# CLOCKANDSWITCH.net
KiCad netlist of a schematic drawn in Altium Designer
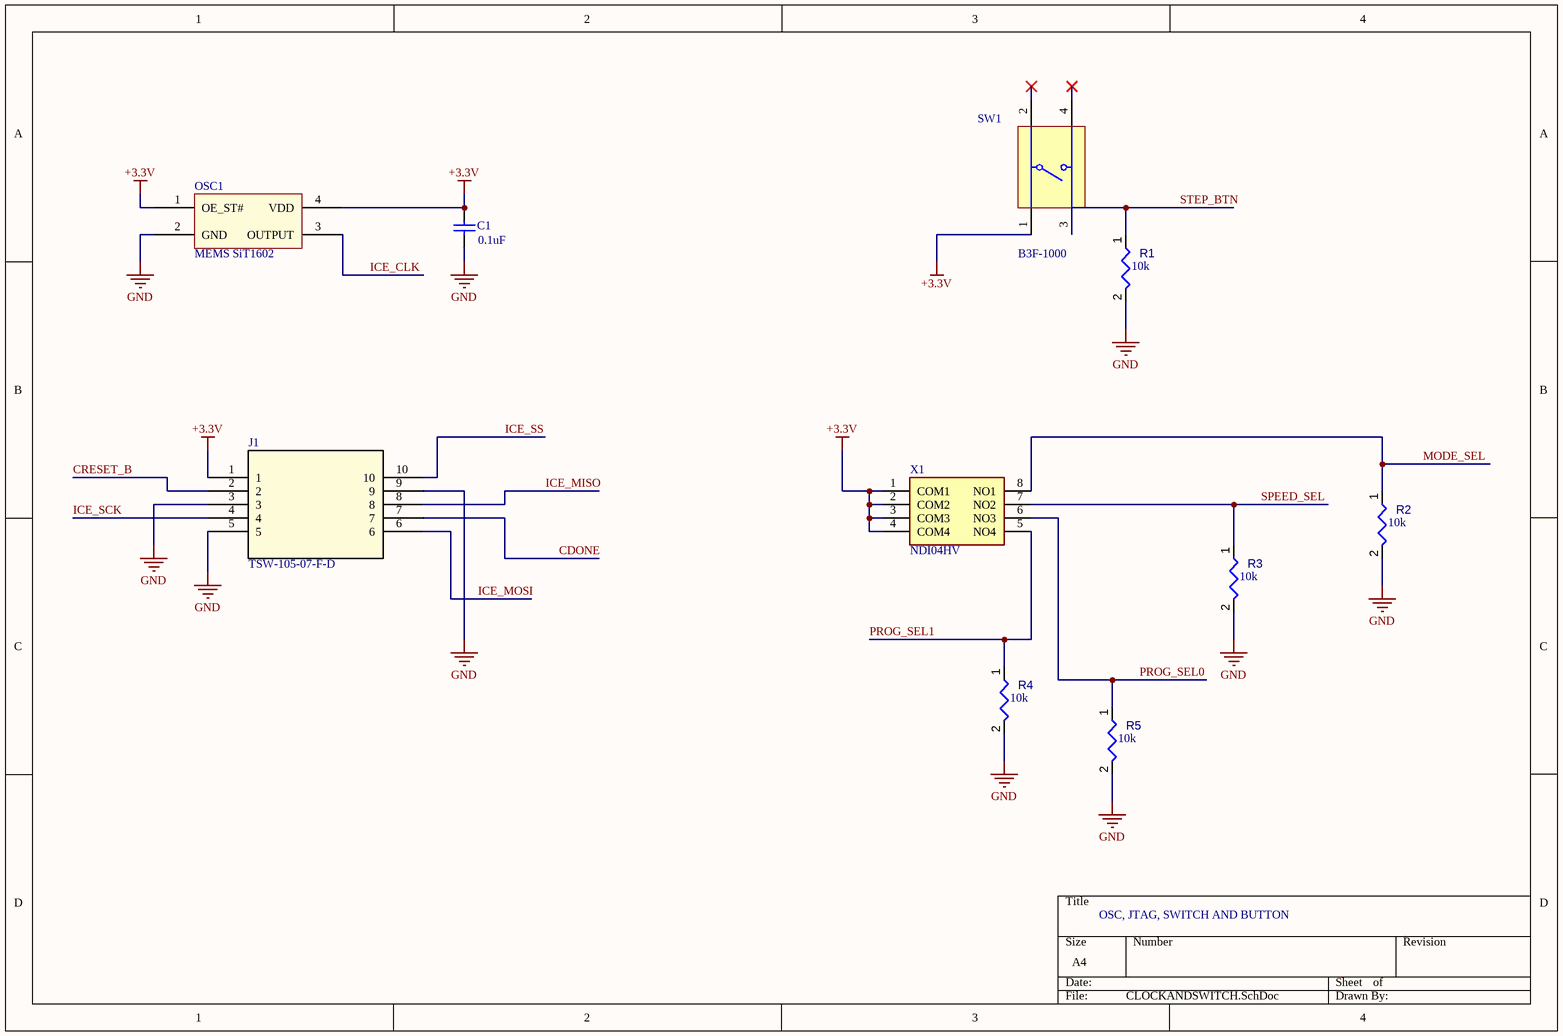
[diagram p0: CLOCKANDSWITCH.SchDoc]

(export (version "E")
  (design (tool "Eeschema 10.0.6"))
  (components
    (comp (ref "C1")
      (value "0.1uF")
      (footprint "C0402")
      (description "Capacitor (Semiconductor SIM Model)")
      (fields
        (field (name "MANUFACTURER") "Samsung Electro-Mechanics")
        (field (name "MANUFACTURER PART NUMBER") "CL05B104KA5NNNC")
        (field (name "PUBLISHER") "Altium Limited")
      )
      (libsource (lib "Miscellaneous Devices") (part "Cap Semi"))
    )
    (comp (ref "J1")
      (value "TSW-105-07-F-D")
      (footprint "TSW-105-07-G-D_SAI")
      (description "Description")
      (fields (field (name "COPYRIGHT") "Copyright (C) 2025 Ultra Librarian. All rights reserved."))
      (libsource (lib "Talha Khan") (part "TSW-105-07-F-D"))
    )
    (comp (ref "OSC1")
      (value "MEMS SiT1602")
      (footprint "oscMEMS1602")
      (description "MEMS OSC XO 12.0000MHZ LVCMOS")
      (fields
        (field (name "MANUFACTURER") "SiTIME")
        (field (name "MANUFACTURER PART NUMBER") "SIT1602AC-13-33E-12.000000G")
      )
      (libsource (lib "FPGAlib") (part "SIT1602AC-13-33E-12.000000G"))
    )
    (comp (ref "R1")
      (value "10k")
      (footprint "RESC2013X50X35ML15T15")
      (description "Chip Resistor, 10 KOhm, +/- 1%, 125 mW, -55 to 155 degC, 0805 (2012 Metric)")
      (fields (field (name "TOLERANCE") "1%") (field (name "POWER") "125mW"))
      (libsource (lib "Talha Khan") (part "RES-2"))
    )
    (comp (ref "R2")
      (value "10k")
      (footprint "RESC2013X50X35ML15T15")
      (description "Chip Resistor, 10 KOhm, +/- 1%, 125 mW, -55 to 155 degC, 0805 (2012 Metric)")
      (fields (field (name "TOLERANCE") "1%") (field (name "POWER") "125mW"))
      (libsource (lib "Talha Khan") (part "RES-2"))
    )
    (comp (ref "R3")
      (value "10k")
      (footprint "RESC2013X50X35ML15T15")
      (description "Chip Resistor, 10 KOhm, +/- 1%, 125 mW, -55 to 155 degC, 0805 (2012 Metric)")
      (fields (field (name "TOLERANCE") "1%") (field (name "POWER") "125mW"))
      (libsource (lib "Talha Khan") (part "RES-2"))
    )
    (comp (ref "R4")
      (value "10k")
      (footprint "RESC2013X50X35ML15T15")
      (description "Chip Resistor, 10 KOhm, +/- 1%, 125 mW, -55 to 155 degC, 0805 (2012 Metric)")
      (fields (field (name "TOLERANCE") "1%") (field (name "POWER") "125mW"))
      (libsource (lib "Talha Khan") (part "RES-2"))
    )
    (comp (ref "R5")
      (value "10k")
      (footprint "RESC2013X50X35ML15T15")
      (description "Chip Resistor, 10 KOhm, +/- 1%, 125 mW, -55 to 155 degC, 0805 (2012 Metric)")
      (fields (field (name "TOLERANCE") "1%") (field (name "POWER") "125mW"))
      (libsource (lib "Talha Khan") (part "RES-2"))
    )
    (comp (ref "SW1")
      (value "B3F-1000")
      (footprint "OMRON-B3F-1000-4_V")
      (description "Tactile Switch, SPST-NO, 0.05 A, 24 V, -25 to 70 degC, 4-Pin THD, RoHS, Bulk")
      (fields (field (name "MANUFACTURER") "Omron Electronic Components"))
      (libsource (lib "Talha Khan") (part "SW-SPST-4_A"))
    )
    (comp (ref "X1")
      (value "NDI04HV")
      (footprint "NDI04HV")
      (description "Dip Switch SPST 4 Position Through Hole Slide (Standard) Actuator 25mA 24VDC")
      (fields (field (name "MOUSER PART NUMBER") "642-NDI04HV"))
      (libsource (lib "Talha Khan") (part "NDI04HV"))
    )
  )
  (nets
    (net (code "1") (name "+3.3V") (class "Default")
      (node (ref "C1") (pin "2") (pinfunction "2_2") (pintype "passive"))
      (node (ref "J1") (pin "1") (pinfunction "1_1") (pintype "passive"))
      (node (ref "OSC1") (pin "1") (pinfunction "OE_ST#_1") (pintype "passive"))
      (node (ref "OSC1") (pin "4") (pinfunction "VDD_4") (pintype "passive"))
      (node (ref "SW1") (pin "1") (pinfunction "1_1") (pintype "passive"))
      (node (ref "X1") (pin "1") (pinfunction "COM1_1") (pintype "passive"))
      (node (ref "X1") (pin "2") (pinfunction "COM2_2") (pintype "passive"))
      (node (ref "X1") (pin "3") (pinfunction "COM3_3") (pintype "passive"))
      (node (ref "X1") (pin "4") (pinfunction "COM4_4") (pintype "passive"))
    )
    (net (code "2") (name "/CDONE") (class "Default")
      (node (ref "J1") (pin "7") (pinfunction "7_7") (pintype "passive"))
    )
    (net (code "3") (name "/CRESET_B") (class "Default")
      (node (ref "J1") (pin "2") (pinfunction "2_2") (pintype "passive"))
    )
    (net (code "4") (name "/ICE_CLK") (class "Default")
      (node (ref "OSC1") (pin "3") (pinfunction "OUTPUT_3") (pintype "passive"))
    )
    (net (code "5") (name "/ICE_MISO") (class "Default")
      (node (ref "J1") (pin "8") (pinfunction "8_8") (pintype "passive"))
    )
    (net (code "6") (name "/ICE_MOSI") (class "Default")
      (node (ref "J1") (pin "6") (pinfunction "6_6") (pintype "passive"))
    )
    (net (code "7") (name "/ICE_SCK") (class "Default")
      (node (ref "J1") (pin "4") (pinfunction "4_4") (pintype "passive"))
    )
    (net (code "8") (name "/ICE_SS") (class "Default")
      (node (ref "J1") (pin "10") (pinfunction "10_10") (pintype "passive"))
    )
    (net (code "9") (name "/MODE_SEL") (class "Default")
      (node (ref "R2") (pin "1") (pinfunction "1_1") (pintype "passive"))
      (node (ref "X1") (pin "8") (pinfunction "NO1_8") (pintype "passive"))
    )
    (net (code "10") (name "/PROG_SEL0") (class "Default")
      (node (ref "R5") (pin "1") (pinfunction "1_1") (pintype "passive"))
      (node (ref "X1") (pin "6") (pinfunction "NO3_6") (pintype "passive"))
    )
    (net (code "11") (name "/PROG_SEL1") (class "Default")
      (node (ref "R4") (pin "1") (pinfunction "1_1") (pintype "passive"))
      (node (ref "X1") (pin "5") (pinfunction "NO4_5") (pintype "passive"))
    )
    (net (code "12") (name "/SPEED_SEL") (class "Default")
      (node (ref "R3") (pin "1") (pinfunction "1_1") (pintype "passive"))
      (node (ref "X1") (pin "7") (pinfunction "NO2_7") (pintype "passive"))
    )
    (net (code "13") (name "/STEP_BTN") (class "Default")
      (node (ref "R1") (pin "1") (pinfunction "1_1") (pintype "passive"))
      (node (ref "SW1") (pin "3") (pinfunction "3_3") (pintype "passive"))
    )
    (net (code "14") (name "GND") (class "Default")
      (node (ref "C1") (pin "1") (pinfunction "1_1") (pintype "passive"))
      (node (ref "J1") (pin "3") (pinfunction "3_3") (pintype "passive"))
      (node (ref "J1") (pin "5") (pinfunction "5_5") (pintype "passive"))
      (node (ref "J1") (pin "9") (pinfunction "9_9") (pintype "passive"))
      (node (ref "OSC1") (pin "2") (pinfunction "GND_2") (pintype "passive"))
      (node (ref "R1") (pin "2") (pinfunction "2_2") (pintype "passive"))
      (node (ref "R2") (pin "2") (pinfunction "2_2") (pintype "passive"))
      (node (ref "R3") (pin "2") (pinfunction "2_2") (pintype "passive"))
      (node (ref "R4") (pin "2") (pinfunction "2_2") (pintype "passive"))
      (node (ref "R5") (pin "2") (pinfunction "2_2") (pintype "passive"))
    )
    (net (code "15") (name "unconnected-(SW1-Pad2)") (class "Default")
      (node (ref "SW1") (pin "2") (pinfunction "2_2") (pintype "passive+no_connect"))
    )
    (net (code "16") (name "unconnected-(SW1-Pad4)") (class "Default")
      (node (ref "SW1") (pin "4") (pinfunction "4_4") (pintype "passive+no_connect"))
    )
  )
)
